# Encoder_Board.net
KiCad netlist of a schematic drawn in EAGLE
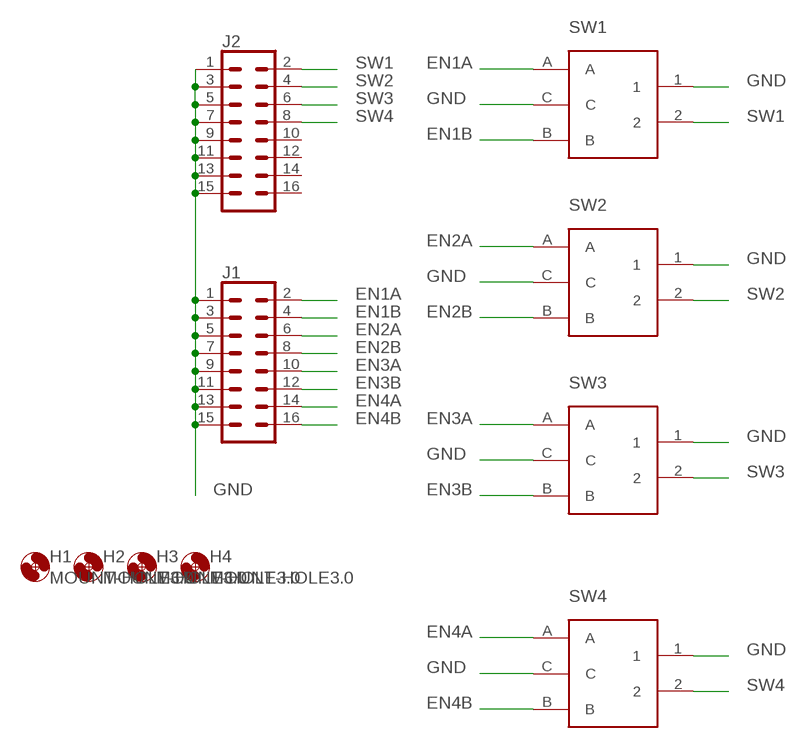
[diagram p0: schematic, sheet 1]

(export (version "E")
  (design (tool "Eeschema 10.0.6"))
  (components
    (comp (ref "H1")
      (value "MOUNT-HOLE3.0")
      (footprint "eagle-import:3,0")
      (libsource (lib "eagle-import") (part "MOUNT-HOLE3.0"))
    )
    (comp (ref "H2")
      (value "MOUNT-HOLE3.0")
      (footprint "eagle-import:3,0")
      (libsource (lib "eagle-import") (part "MOUNT-HOLE3.0"))
    )
    (comp (ref "H3")
      (value "MOUNT-HOLE3.0")
      (footprint "eagle-import:3,0")
      (libsource (lib "eagle-import") (part "MOUNT-HOLE3.0"))
    )
    (comp (ref "H4")
      (value "MOUNT-HOLE3.0")
      (footprint "eagle-import:3,0")
      (libsource (lib "eagle-import") (part "MOUNT-HOLE3.0"))
    )
    (comp (ref "J1")
      (value "CONN_08X2")
      (footprint "eagle-import:2X8")
      (libsource (lib "eagle-import") (part "CONN_08X2"))
    )
    (comp (ref "J2")
      (value "CONN_08X2")
      (footprint "eagle-import:2X8")
      (libsource (lib "eagle-import") (part "CONN_08X2"))
    )
    (comp (ref "SW1")
      (value "PEC11R-4220F-S0012-ND")
      (footprint "eagle-import:PEC11R-4XXXF-SXXXX")
      (libsource (lib "eagle-import") (part "PEC11R-4220F-S0012-ND"))
    )
    (comp (ref "SW2")
      (value "PEC11R-4220F-S0012-ND")
      (footprint "eagle-import:PEC11R-4XXXF-SXXXX")
      (libsource (lib "eagle-import") (part "PEC11R-4220F-S0012-ND"))
    )
    (comp (ref "SW3")
      (value "PEC11R-4220F-S0012-ND")
      (footprint "eagle-import:PEC11R-4XXXF-SXXXX")
      (libsource (lib "eagle-import") (part "PEC11R-4220F-S0012-ND"))
    )
    (comp (ref "SW4")
      (value "PEC11R-4220F-S0012-ND")
      (footprint "eagle-import:PEC11R-4XXXF-SXXXX")
      (libsource (lib "eagle-import") (part "PEC11R-4220F-S0012-ND"))
    )
  )
  (nets
    (net (code "1") (name "/EN1A") (class "Default")
      (node (ref "J1") (pin "2") (pinfunction "2_2") (pintype "passive"))
      (node (ref "SW1") (pin "A") (pinfunction "A_A") (pintype "bidirectional"))
    )
    (net (code "2") (name "/EN1B") (class "Default")
      (node (ref "J1") (pin "4") (pinfunction "4_4") (pintype "passive"))
      (node (ref "SW1") (pin "B") (pinfunction "B_B") (pintype "bidirectional"))
    )
    (net (code "3") (name "/EN2A") (class "Default")
      (node (ref "J1") (pin "6") (pinfunction "6_6") (pintype "passive"))
      (node (ref "SW2") (pin "A") (pinfunction "A_A") (pintype "bidirectional"))
    )
    (net (code "4") (name "/EN2B") (class "Default")
      (node (ref "J1") (pin "8") (pinfunction "8_8") (pintype "passive"))
      (node (ref "SW2") (pin "B") (pinfunction "B_B") (pintype "bidirectional"))
    )
    (net (code "5") (name "/EN3A") (class "Default")
      (node (ref "J1") (pin "10") (pinfunction "10_10") (pintype "passive"))
      (node (ref "SW3") (pin "A") (pinfunction "A_A") (pintype "bidirectional"))
    )
    (net (code "6") (name "/EN3B") (class "Default")
      (node (ref "J1") (pin "12") (pinfunction "12_12") (pintype "passive"))
      (node (ref "SW3") (pin "B") (pinfunction "B_B") (pintype "bidirectional"))
    )
    (net (code "7") (name "/EN4A") (class "Default")
      (node (ref "J1") (pin "14") (pinfunction "14_14") (pintype "passive"))
      (node (ref "SW4") (pin "A") (pinfunction "A_A") (pintype "bidirectional"))
    )
    (net (code "8") (name "/EN4B") (class "Default")
      (node (ref "J1") (pin "16") (pinfunction "16_16") (pintype "passive"))
      (node (ref "SW4") (pin "B") (pinfunction "B_B") (pintype "bidirectional"))
    )
    (net (code "9") (name "/GND") (class "Default")
      (node (ref "J1") (pin "1") (pinfunction "1_1") (pintype "passive"))
      (node (ref "J1") (pin "11") (pinfunction "11_11") (pintype "passive"))
      (node (ref "J1") (pin "13") (pinfunction "13_13") (pintype "passive"))
      (node (ref "J1") (pin "15") (pinfunction "15_15") (pintype "passive"))
      (node (ref "J1") (pin "3") (pinfunction "3_3") (pintype "passive"))
      (node (ref "J1") (pin "5") (pinfunction "5_5") (pintype "passive"))
      (node (ref "J1") (pin "7") (pinfunction "7_7") (pintype "passive"))
      (node (ref "J1") (pin "9") (pinfunction "9_9") (pintype "passive"))
      (node (ref "J2") (pin "1") (pinfunction "1_1") (pintype "passive"))
      (node (ref "J2") (pin "11") (pinfunction "11_11") (pintype "passive"))
      (node (ref "J2") (pin "13") (pinfunction "13_13") (pintype "passive"))
      (node (ref "J2") (pin "15") (pinfunction "15_15") (pintype "passive"))
      (node (ref "J2") (pin "3") (pinfunction "3_3") (pintype "passive"))
      (node (ref "J2") (pin "5") (pinfunction "5_5") (pintype "passive"))
      (node (ref "J2") (pin "7") (pinfunction "7_7") (pintype "passive"))
      (node (ref "J2") (pin "9") (pinfunction "9_9") (pintype "passive"))
      (node (ref "SW1") (pin "1") (pinfunction "1_1") (pintype "bidirectional"))
      (node (ref "SW1") (pin "C") (pinfunction "C_C") (pintype "bidirectional"))
      (node (ref "SW2") (pin "1") (pinfunction "1_1") (pintype "bidirectional"))
      (node (ref "SW2") (pin "C") (pinfunction "C_C") (pintype "bidirectional"))
      (node (ref "SW3") (pin "1") (pinfunction "1_1") (pintype "bidirectional"))
      (node (ref "SW3") (pin "C") (pinfunction "C_C") (pintype "bidirectional"))
      (node (ref "SW4") (pin "1") (pinfunction "1_1") (pintype "bidirectional"))
      (node (ref "SW4") (pin "C") (pinfunction "C_C") (pintype "bidirectional"))
    )
    (net (code "10") (name "/SW1") (class "Default")
      (node (ref "J2") (pin "2") (pinfunction "2_2") (pintype "passive"))
      (node (ref "SW1") (pin "2") (pinfunction "2_2") (pintype "bidirectional"))
    )
    (net (code "11") (name "/SW2") (class "Default")
      (node (ref "J2") (pin "4") (pinfunction "4_4") (pintype "passive"))
      (node (ref "SW2") (pin "2") (pinfunction "2_2") (pintype "bidirectional"))
    )
    (net (code "12") (name "/SW3") (class "Default")
      (node (ref "J2") (pin "6") (pinfunction "6_6") (pintype "passive"))
      (node (ref "SW3") (pin "2") (pinfunction "2_2") (pintype "bidirectional"))
    )
    (net (code "13") (name "/SW4") (class "Default")
      (node (ref "J2") (pin "8") (pinfunction "8_8") (pintype "passive"))
      (node (ref "SW4") (pin "2") (pinfunction "2_2") (pintype "bidirectional"))
    )
    (net (code "14") (name "unconnected-(J2-Pad10)") (class "Default")
      (node (ref "J2") (pin "10") (pinfunction "10_10") (pintype "passive"))
    )
    (net (code "15") (name "unconnected-(J2-Pad12)") (class "Default")
      (node (ref "J2") (pin "12") (pinfunction "12_12") (pintype "passive"))
    )
    (net (code "16") (name "unconnected-(J2-Pad14)") (class "Default")
      (node (ref "J2") (pin "14") (pinfunction "14_14") (pintype "passive"))
    )
    (net (code "17") (name "unconnected-(J2-Pad16)") (class "Default")
      (node (ref "J2") (pin "16") (pinfunction "16_16") (pintype "passive"))
    )
  )
)
